# sa612_upconverter.net
KiCad netlist of a schematic drawn in EAGLE
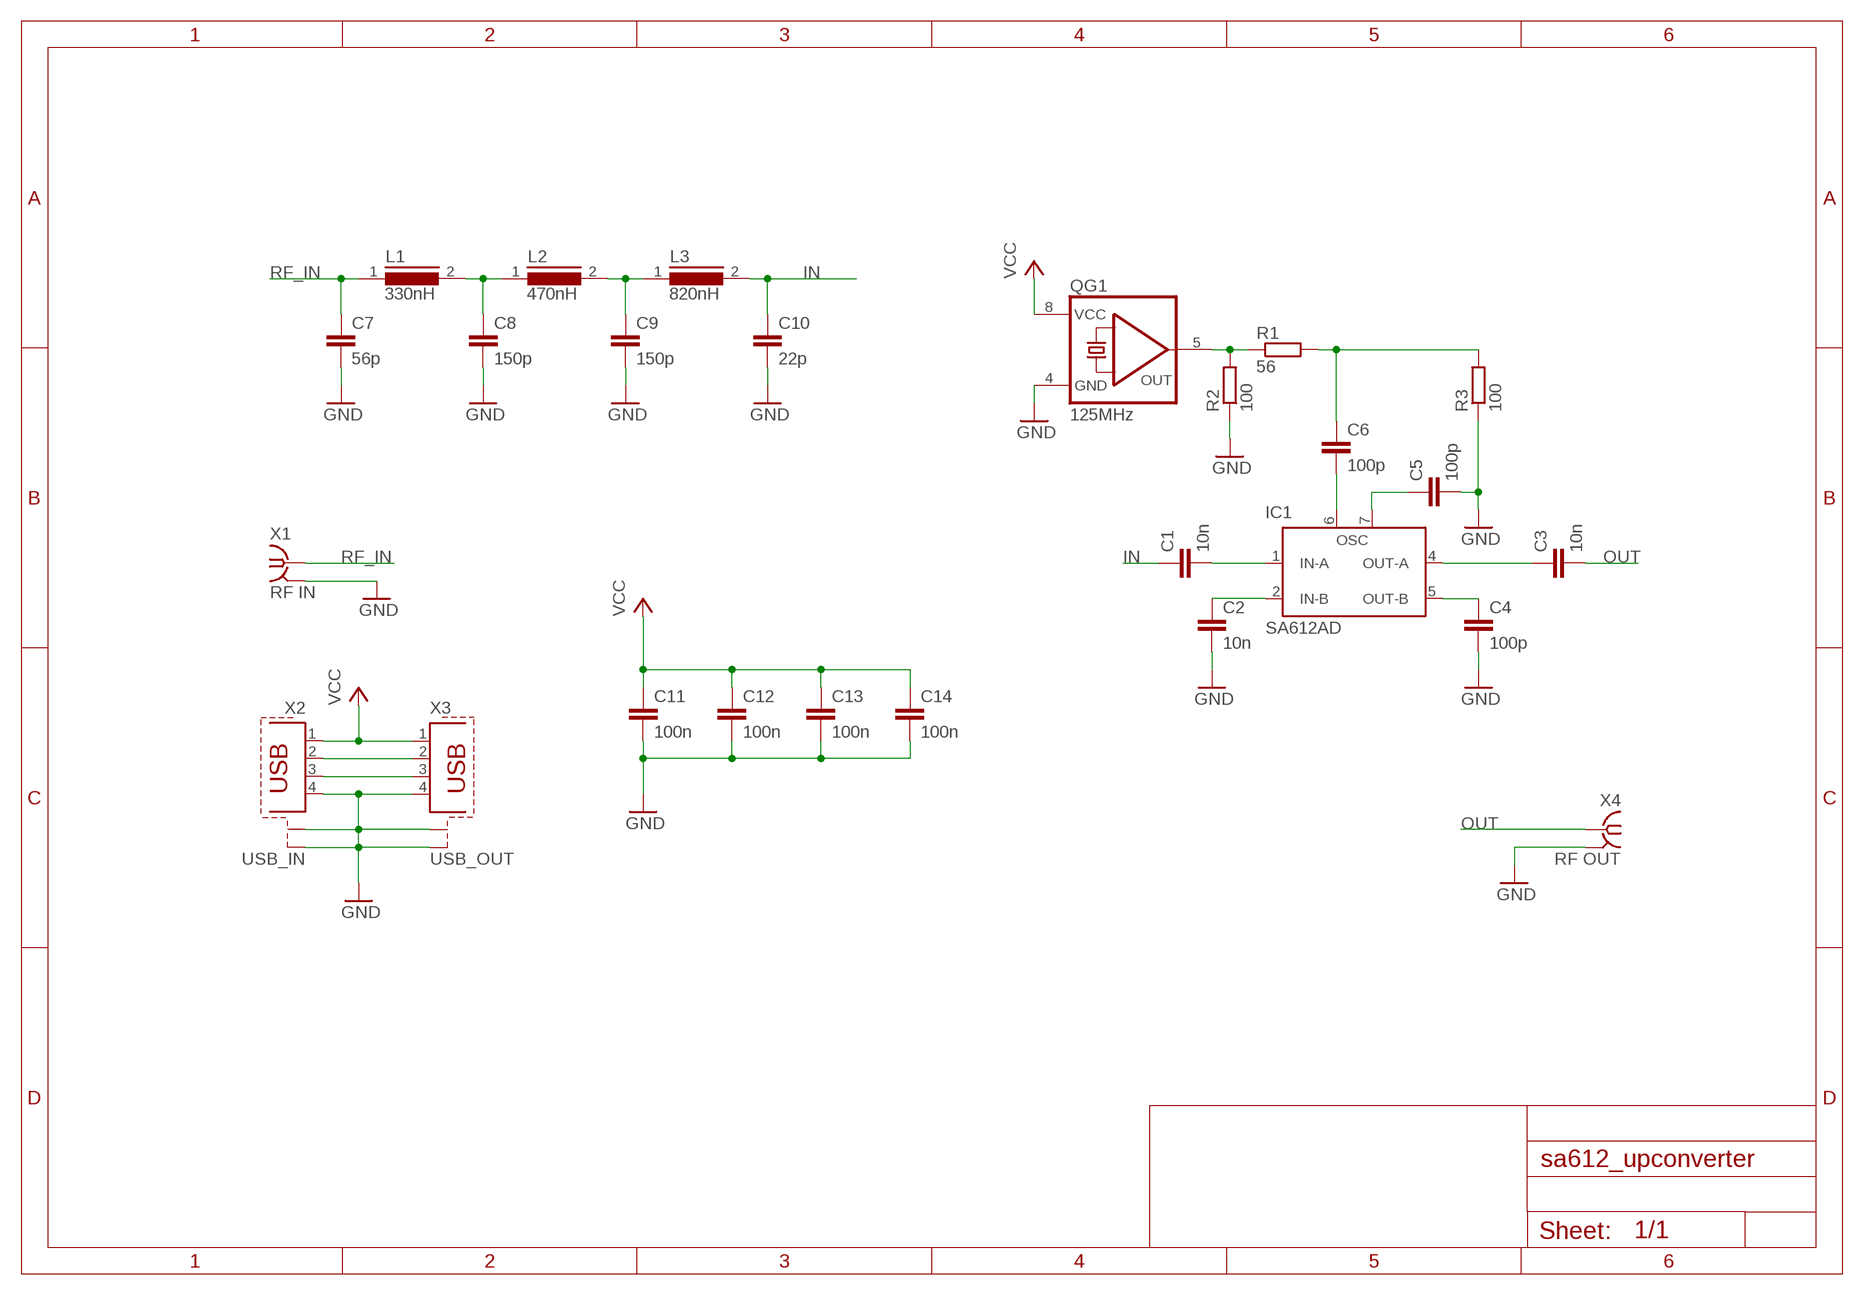
[diagram p0: schematic, sheet 1]

(export (version "E")
  (design (tool "Eeschema 10.0.6"))
  (components
    (comp (ref "C1")
      (value "10n")
      (footprint "eagle-import:C2.5-2")
      (libsource (lib "eagle-import") (part "C2.5/2"))
    )
    (comp (ref "C2")
      (value "10n")
      (footprint "eagle-import:C2.5-2")
      (libsource (lib "eagle-import") (part "C2.5/2"))
    )
    (comp (ref "C3")
      (value "10n")
      (footprint "eagle-import:C2.5-2")
      (libsource (lib "eagle-import") (part "C2.5/2"))
    )
    (comp (ref "C4")
      (value "100p")
      (footprint "eagle-import:C2.5-2")
      (libsource (lib "eagle-import") (part "C2.5/2"))
    )
    (comp (ref "C5")
      (value "100p")
      (footprint "eagle-import:C7.5B3")
      (libsource (lib "eagle-import") (part "C7.5/3"))
    )
    (comp (ref "C6")
      (value "100p")
      (footprint "eagle-import:C2.5-2")
      (libsource (lib "eagle-import") (part "C2.5/2"))
    )
    (comp (ref "C7")
      (value "56p")
      (footprint "eagle-import:C2.5-2")
      (libsource (lib "eagle-import") (part "C2.5/2"))
    )
    (comp (ref "C8")
      (value "150p")
      (footprint "eagle-import:C2.5-2")
      (libsource (lib "eagle-import") (part "C2.5/2"))
    )
    (comp (ref "C9")
      (value "150p")
      (footprint "eagle-import:C2.5-2")
      (libsource (lib "eagle-import") (part "C2.5/2"))
    )
    (comp (ref "C10")
      (value "22p")
      (footprint "eagle-import:C2.5-2")
      (libsource (lib "eagle-import") (part "C2.5/2"))
    )
    (comp (ref "C11")
      (value "100n")
      (footprint "eagle-import:C2.5-2")
      (libsource (lib "eagle-import") (part "C2.5/2"))
    )
    (comp (ref "C12")
      (value "100n")
      (footprint "eagle-import:C2.5-2")
      (libsource (lib "eagle-import") (part "C2.5/2"))
    )
    (comp (ref "C13")
      (value "100n")
      (footprint "eagle-import:C2.5-2")
      (libsource (lib "eagle-import") (part "C2.5/2"))
    )
    (comp (ref "C14")
      (value "100n")
      (footprint "eagle-import:C2.5-2")
      (libsource (lib "eagle-import") (part "C2.5/2"))
    )
    (comp (ref "IC1")
      (value "SA612AD")
      (footprint "eagle-import:SO08")
      (libsource (lib "eagle-import") (part "SA612AD"))
    )
    (comp (ref "L1")
      (value "330nH")
      (footprint "eagle-import:ED16")
      (libsource (lib "eagle-import") (part "ED16"))
    )
    (comp (ref "L2")
      (value "470nH")
      (footprint "eagle-import:ED16")
      (libsource (lib "eagle-import") (part "ED16"))
    )
    (comp (ref "L3")
      (value "820nH")
      (footprint "eagle-import:ED16")
      (libsource (lib "eagle-import") (part "ED16"))
    )
    (comp (ref "QG1")
      (value "125MHz")
      (footprint "eagle-import:DIL08S")
      (libsource (lib "eagle-import") (part "QG5460"))
    )
    (comp (ref "R1")
      (value "56")
      (footprint "eagle-import:0204_7")
      (libsource (lib "eagle-import") (part "R-EU_0204/7"))
    )
    (comp (ref "R2")
      (value "100")
      (footprint "eagle-import:0204_7")
      (libsource (lib "eagle-import") (part "R-EU_0204/7"))
    )
    (comp (ref "R3")
      (value "100")
      (footprint "eagle-import:0204_7")
      (libsource (lib "eagle-import") (part "R-EU_0204/7"))
    )
    (comp (ref "X1")
      (value "RF IN")
      (footprint "eagle-import:BU-SMA-H")
      (libsource (lib "eagle-import") (part "BU-SMA-H"))
    )
    (comp (ref "X2")
      (value "USB_IN")
      (footprint "eagle-import:PN61729-S")
      (libsource (lib "eagle-import") (part "PN61729-S"))
    )
    (comp (ref "X3")
      (value "USB_OUT")
      (footprint "eagle-import:PN87520-S")
      (libsource (lib "eagle-import") (part "PN87520-S"))
    )
    (comp (ref "X4")
      (value "RF OUT")
      (footprint "eagle-import:BU-SMA-V")
      (libsource (lib "eagle-import") (part "BU-SMA-V"))
    )
  )
  (nets
    (net (code "1") (name "/IN") (class "Default")
      (node (ref "C1") (pin "1") (pinfunction "1_1") (pintype "passive"))
      (node (ref "C10") (pin "1") (pinfunction "1_1") (pintype "passive"))
      (node (ref "L3") (pin "2") (pinfunction "2_2") (pintype "passive"))
    )
    (net (code "2") (name "/OUT") (class "Default")
      (node (ref "C3") (pin "2") (pinfunction "2_2") (pintype "passive"))
      (node (ref "X4") (pin "1") (pinfunction "1_1") (pintype "passive"))
    )
    (net (code "3") (name "/RF_IN") (class "Default")
      (node (ref "C7") (pin "1") (pinfunction "1_1") (pintype "passive"))
      (node (ref "L1") (pin "1") (pinfunction "1_1") (pintype "passive"))
      (node (ref "X1") (pin "1") (pinfunction "1_1") (pintype "passive"))
    )
    (net (code "4") (name "GND") (class "Default")
      (node (ref "C10") (pin "2") (pinfunction "2_2") (pintype "passive"))
      (node (ref "C11") (pin "2") (pinfunction "2_2") (pintype "passive"))
      (node (ref "C12") (pin "2") (pinfunction "2_2") (pintype "passive"))
      (node (ref "C13") (pin "2") (pinfunction "2_2") (pintype "passive"))
      (node (ref "C14") (pin "2") (pinfunction "2_2") (pintype "passive"))
      (node (ref "C2") (pin "2") (pinfunction "2_2") (pintype "passive"))
      (node (ref "C4") (pin "2") (pinfunction "2_2") (pintype "passive"))
      (node (ref "C5") (pin "2") (pinfunction "2_2") (pintype "passive"))
      (node (ref "C7") (pin "2") (pinfunction "2_2") (pintype "passive"))
      (node (ref "C8") (pin "2") (pinfunction "2_2") (pintype "passive"))
      (node (ref "C9") (pin "2") (pinfunction "2_2") (pintype "passive"))
      (node (ref "QG1") (pin "4") (pinfunction "GND_4") (pintype "power_in"))
      (node (ref "R2") (pin "1") (pinfunction "1_1") (pintype "passive"))
      (node (ref "R3") (pin "1") (pinfunction "1_1") (pintype "passive"))
      (node (ref "X1") (pin "2") (pinfunction "2_2") (pintype "passive"))
      (node (ref "X1") (pin "3") (pinfunction "2_3") (pintype "passive"))
      (node (ref "X1") (pin "4") (pinfunction "2_4") (pintype "passive"))
      (node (ref "X1") (pin "5") (pinfunction "2_5") (pintype "passive"))
      (node (ref "X2") (pin "4") (pinfunction "4_4") (pintype "passive"))
      (node (ref "X2") (pin "S1") (pinfunction "S1_S1") (pintype "passive"))
      (node (ref "X2") (pin "S2") (pinfunction "S2_S2") (pintype "passive"))
      (node (ref "X3") (pin "4") (pinfunction "4_4") (pintype "passive"))
      (node (ref "X3") (pin "S1") (pinfunction "S1_S1") (pintype "passive"))
      (node (ref "X3") (pin "S2") (pinfunction "S2_S2") (pintype "passive"))
      (node (ref "X4") (pin "2") (pinfunction "2_2") (pintype "passive"))
      (node (ref "X4") (pin "3") (pinfunction "2_3") (pintype "passive"))
      (node (ref "X4") (pin "4") (pinfunction "2_4") (pintype "passive"))
      (node (ref "X4") (pin "5") (pinfunction "2_5") (pintype "passive"))
    )
    (net (code "5") (name "Net-(C6-Pad1)") (class "Default")
      (node (ref "C6") (pin "1") (pinfunction "1_1") (pintype "passive"))
      (node (ref "R1") (pin "2") (pinfunction "2_2") (pintype "passive"))
      (node (ref "R3") (pin "2") (pinfunction "2_2") (pintype "passive"))
    )
    (net (code "6") (name "Net-(C8-Pad1)") (class "Default")
      (node (ref "C8") (pin "1") (pinfunction "1_1") (pintype "passive"))
      (node (ref "L1") (pin "2") (pinfunction "2_2") (pintype "passive"))
      (node (ref "L2") (pin "1") (pinfunction "1_1") (pintype "passive"))
    )
    (net (code "7") (name "Net-(C9-Pad1)") (class "Default")
      (node (ref "C9") (pin "1") (pinfunction "1_1") (pintype "passive"))
      (node (ref "L2") (pin "2") (pinfunction "2_2") (pintype "passive"))
      (node (ref "L3") (pin "1") (pinfunction "1_1") (pintype "passive"))
    )
    (net (code "8") (name "Net-(IC1A-IN-A)") (class "Default")
      (node (ref "C1") (pin "2") (pinfunction "2_2") (pintype "passive"))
      (node (ref "IC1") (pin "1") (pinfunction "IN-A_1") (pintype "input"))
    )
    (net (code "9") (name "Net-(IC1A-IN-B)") (class "Default")
      (node (ref "C2") (pin "1") (pinfunction "1_1") (pintype "passive"))
      (node (ref "IC1") (pin "2") (pinfunction "IN-B_2") (pintype "input"))
    )
    (net (code "10") (name "Net-(IC1A-OSC')") (class "Default")
      (node (ref "C5") (pin "1") (pinfunction "1_1") (pintype "passive"))
      (node (ref "IC1") (pin "7") (pinfunction "OSC'_7") (pintype "passive"))
    )
    (net (code "11") (name "Net-(IC1A-OSC)") (class "Default")
      (node (ref "C6") (pin "2") (pinfunction "2_2") (pintype "passive"))
      (node (ref "IC1") (pin "6") (pinfunction "OSC_6") (pintype "passive"))
    )
    (net (code "12") (name "Net-(IC1A-OUT-A)") (class "Default")
      (node (ref "C3") (pin "1") (pinfunction "1_1") (pintype "passive"))
      (node (ref "IC1") (pin "4") (pinfunction "OUT-A_4") (pintype "input"))
    )
    (net (code "13") (name "Net-(IC1A-OUT-B)") (class "Default")
      (node (ref "C4") (pin "1") (pinfunction "1_1") (pintype "passive"))
      (node (ref "IC1") (pin "5") (pinfunction "OUT-B_5") (pintype "input"))
    )
    (net (code "14") (name "Net-(QG1-OUT)") (class "Default")
      (node (ref "QG1") (pin "5") (pinfunction "OUT_5") (pintype "output"))
      (node (ref "R1") (pin "1") (pinfunction "1_1") (pintype "passive"))
      (node (ref "R2") (pin "2") (pinfunction "2_2") (pintype "passive"))
    )
    (net (code "15") (name "Net-(X2-Pad2)") (class "Default")
      (node (ref "X2") (pin "2") (pinfunction "2_2") (pintype "passive"))
      (node (ref "X3") (pin "2") (pinfunction "2_2") (pintype "passive"))
    )
    (net (code "16") (name "Net-(X2-Pad3)") (class "Default")
      (node (ref "X2") (pin "3") (pinfunction "3_3") (pintype "passive"))
      (node (ref "X3") (pin "3") (pinfunction "3_3") (pintype "passive"))
    )
    (net (code "17") (name "VCC") (class "Default")
      (node (ref "C11") (pin "1") (pinfunction "1_1") (pintype "passive"))
      (node (ref "C12") (pin "1") (pinfunction "1_1") (pintype "passive"))
      (node (ref "C13") (pin "1") (pinfunction "1_1") (pintype "passive"))
      (node (ref "C14") (pin "1") (pinfunction "1_1") (pintype "passive"))
      (node (ref "QG1") (pin "8") (pinfunction "VCC_8") (pintype "power_in"))
      (node (ref "X2") (pin "1") (pinfunction "1_1") (pintype "passive"))
      (node (ref "X3") (pin "1") (pinfunction "1_1") (pintype "passive"))
    )
  )
)
